# MICRO_AND_VREF.net
KiCad netlist of a schematic drawn in Altium Designer
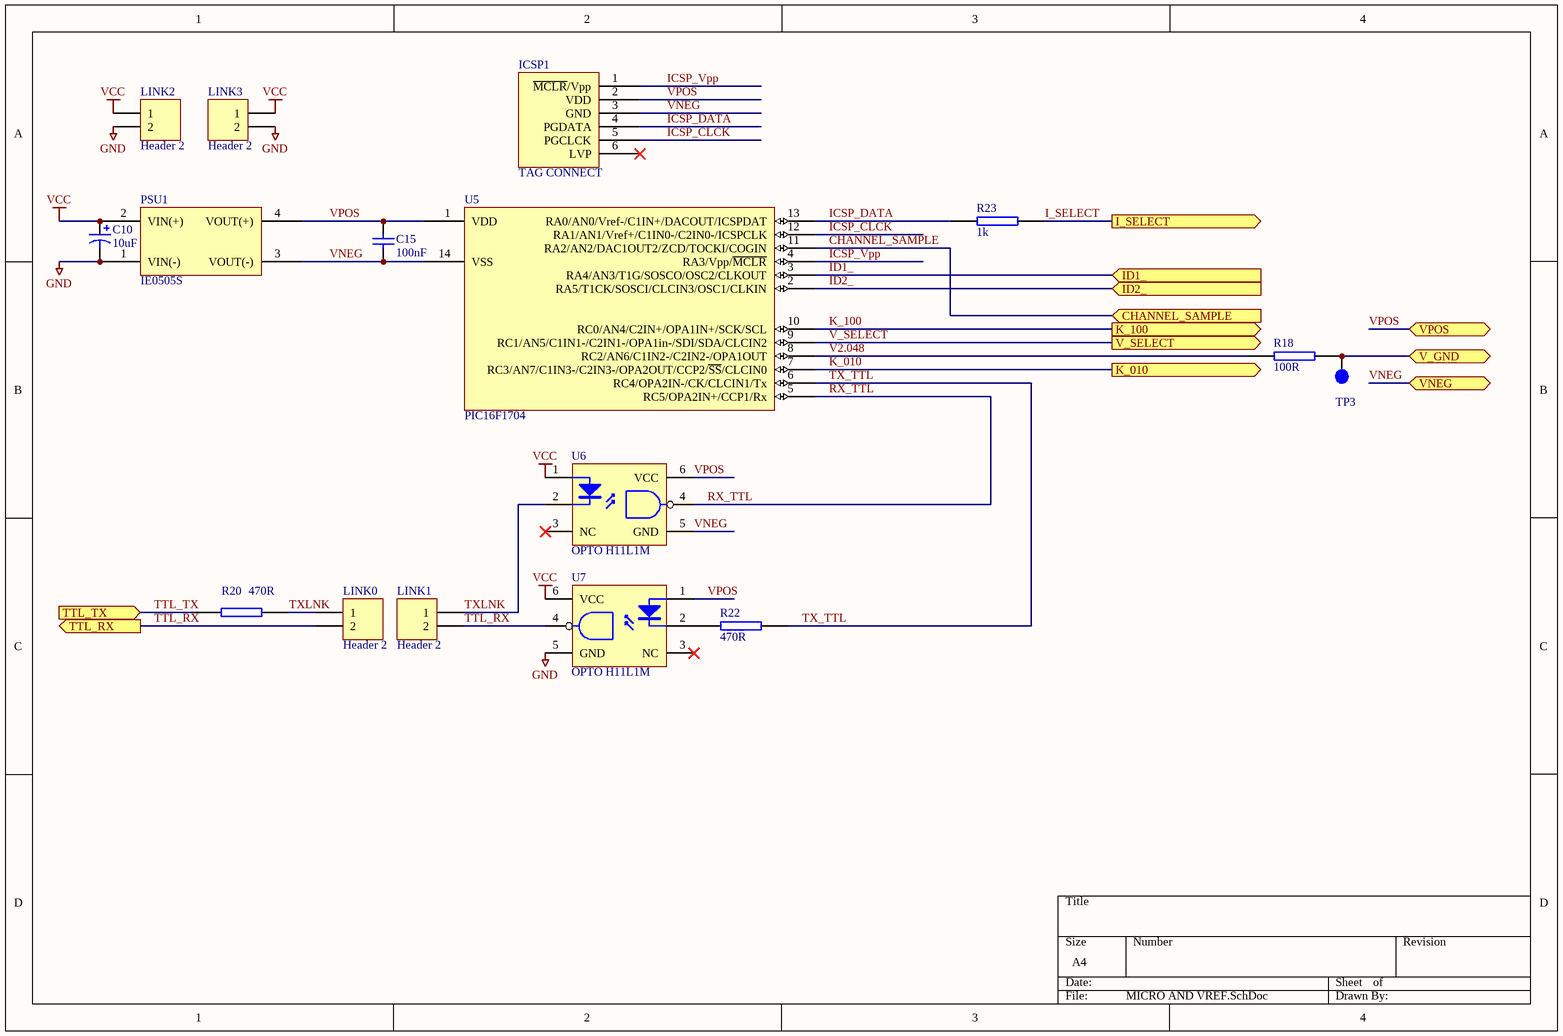
[diagram p0: MICRO AND VREF.SchDoc]

(export (version "E")
  (design (tool "Eeschema 10.0.6"))
  (components
    (comp (ref "C10")
      (value "10uF")
      (footprint "CAP ELECTRO SIZE-B")
      (description "Polarized Capacitor (Radial)")
      (libsource (lib "Miscellaneous Devices") (part "Cap Pol1"))
    )
    (comp (ref "C15")
      (value "100nF")
      (footprint "CAP (3D) - 0603")
      (description "Capacitor")
      (libsource (lib "Miscellaneous Devices") (part "Cap"))
    )
    (comp (ref "ICSP1")
      (value "TAG CONNECT")
      (footprint "ICSP - TAG CONNECT TYPE2")
      (fields (field (name "MANUFACTURER") "N/A - PCB ARTWORK"))
      (libsource (lib "I2C PENDANT") (part "ICSP - TAG CONNECT"))
    )
    (comp (ref "LINK0")
      (value "Header 2")
      (footprint "HDR1X2")
      (description "Header, 2-Pin")
      (fields (field (name "PUBLISHER") "Altium Limited"))
      (libsource (lib "Miscellaneous Connectors") (part "Header 2"))
    )
    (comp (ref "LINK1")
      (value "Header 2")
      (footprint "HDR1X2")
      (description "Header, 2-Pin")
      (fields (field (name "PUBLISHER") "Altium Limited"))
      (libsource (lib "") (part "Header 2_1"))
    )
    (comp (ref "LINK2")
      (value "Header 2")
      (footprint "HDR1X2")
      (description "Header, 2-Pin")
      (fields (field (name "PUBLISHER") "Altium Limited"))
      (libsource (lib "Miscellaneous Connectors") (part "Header 2"))
    )
    (comp (ref "LINK3")
      (value "Header 2")
      (footprint "HDR1X2")
      (description "Header, 2-Pin")
      (fields (field (name "PUBLISHER") "Altium Limited"))
      (libsource (lib "") (part "Header 2_1"))
    )
    (comp (ref "PSU1")
      (value "IE0505S")
      (footprint "IE0505S")
      (description "XP POWER IE0505S")
      (fields (field (name "FARNELL PART NO.") "8727694") (field (name "MANUFACTURER") "XP POWER"))
      (libsource (lib "Schlib1") (part "5V ISOLATED"))
    )
    (comp (ref "R18")
      (value "100R")
      (footprint "RES (3D) - 0603")
      (description "RESISTOR SMD 0603")
      (libsource (lib "NASCO") (part "RES SMD 0603"))
    )
    (comp (ref "R20")
      (value "470R")
      (footprint "RES (3D) - 0603")
      (description "RESISTOR SMD 0603 1k")
      (libsource (lib "NASCO Resistors") (part "RES SMD 0603 1k"))
    )
    (comp (ref "R22")
      (value "470R")
      (footprint "RES (3D) - 0603")
      (description "RESISTOR SMD 0603 1k")
      (libsource (lib "NASCO Resistors") (part "RES SMD 0603 1k"))
    )
    (comp (ref "R23")
      (value "1k")
      (footprint "RES (3D) - 0603")
      (description "RESISTOR SMD 0603")
      (libsource (lib "NASCO") (part "RES SMD 0603"))
    )
    (comp (ref "TP3") (value "TestPoint") (footprint "TP") (libsource (lib "NASCO") (part "TestPoint")))
    (comp (ref "U5")
      (value "PIC16F1704")
      (footprint "SOIC-14")
      (libsource (lib "Schlib1") (part "PIC16F1704"))
    )
    (comp (ref "U6")
      (value "OPTO H11L1M")
      (footprint "DIP_6")
      (description "6-Pin Logic Output Optocoupler")
      (libsource (lib "Schlib1") (part "H11L1M"))
    )
    (comp (ref "U7")
      (value "OPTO H11L1M")
      (footprint "DIP_6")
      (description "6-Pin Logic Output Optocoupler")
      (libsource (lib "") (part "H11L1M_1"))
    )
  )
  (nets
    (net (code "1") (name "/CHANNEL_SAMPLE") (class "Default")
      (node (ref "U5") (pin "11") (pinfunction "RA2/AN2/DAC1OUT2/ZCD/TOCKI/COGIN_11") (pintype "bidirectional"))
    )
    (net (code "2") (name "/ICSP_CLCK") (class "Default")
      (node (ref "ICSP1") (pin "5") (pinfunction "PGCLCK_5") (pintype "passive"))
      (node (ref "U5") (pin "12") (pinfunction "RA1/AN1/Vref+/C1IN0-/C2IN0-/ICSPCLK_12") (pintype "bidirectional"))
    )
    (net (code "3") (name "/ICSP_DATA") (class "Default")
      (node (ref "ICSP1") (pin "4") (pinfunction "PGDATA_4") (pintype "passive"))
      (node (ref "R23") (pin "1") (pinfunction "1_1") (pintype "passive"))
      (node (ref "U5") (pin "13") (pinfunction "RA0/AN0/Vref-/C1IN+/DACOUT/ICSPDAT_13") (pintype "bidirectional"))
    )
    (net (code "4") (name "/ICSP_Vpp") (class "Default")
      (node (ref "ICSP1") (pin "1") (pinfunction "~{MCLR}/Vpp_1") (pintype "passive"))
      (node (ref "U5") (pin "4") (pinfunction "RA3/Vpp/~{MCLR}_4") (pintype "bidirectional"))
    )
    (net (code "5") (name "/ID1_") (class "Default")
      (node (ref "U5") (pin "3") (pinfunction "RA4/AN3/T1G/SOSCO/OSC2/CLKOUT_3") (pintype "bidirectional"))
    )
    (net (code "6") (name "/ID2_") (class "Default")
      (node (ref "U5") (pin "2") (pinfunction "RA5/T1CK/SOSCI/CLCIN3/OSC1/CLKIN_2") (pintype "bidirectional"))
    )
    (net (code "7") (name "/I_SELECT") (class "Default")
      (node (ref "R23") (pin "2") (pinfunction "2_2") (pintype "passive"))
    )
    (net (code "8") (name "/K_010") (class "Default")
      (node (ref "U5") (pin "7") (pinfunction "RC3/AN7/C1IN3-/C2IN3-/OPA2OUT/CCP2/~{SS}/CLCIN0_7") (pintype "bidirectional"))
    )
    (net (code "9") (name "/K_100") (class "Default")
      (node (ref "U5") (pin "10") (pinfunction "RC0/AN4/C2IN+/OPA1IN+/SCK/SCL_10") (pintype "bidirectional"))
    )
    (net (code "10") (name "/RX_TTL") (class "Default")
      (node (ref "U5") (pin "5") (pinfunction "RC5/OPA2IN+/CCP1/Rx_5") (pintype "bidirectional"))
      (node (ref "U6") (pin "4") (pinfunction "Q_4") (pintype "passive"))
    )
    (net (code "11") (name "/TTL_RX") (class "Default")
      (node (ref "LINK0") (pin "2") (pinfunction "2_2") (pintype "passive"))
      (node (ref "LINK1") (pin "2") (pinfunction "2_2") (pintype "passive"))
      (node (ref "U7") (pin "4") (pinfunction "Q_4") (pintype "passive"))
    )
    (net (code "12") (name "/TTL_TX") (class "Default")
      (node (ref "R20") (pin "1") (pinfunction "1_1") (pintype "passive"))
    )
    (net (code "13") (name "/TXLNK") (class "Default")
      (node (ref "LINK0") (pin "1") (pinfunction "1_1") (pintype "passive"))
      (node (ref "LINK1") (pin "1") (pinfunction "1_1") (pintype "passive"))
      (node (ref "R20") (pin "2") (pinfunction "2_2") (pintype "passive"))
      (node (ref "U6") (pin "2") (pinfunction "K_2") (pintype "passive"))
    )
    (net (code "14") (name "/TX_TTL") (class "Default")
      (node (ref "R22") (pin "2") (pinfunction "2_2") (pintype "passive"))
      (node (ref "U5") (pin "6") (pinfunction "RC4/OPA2IN-/CK/CLCIN1/Tx_6") (pintype "bidirectional"))
    )
    (net (code "15") (name "/V2.048") (class "Default")
      (node (ref "R18") (pin "1") (pinfunction "1_1") (pintype "passive"))
      (node (ref "U5") (pin "8") (pinfunction "RC2/AN6/C1IN2-/C2IN2-/OPA1OUT_8") (pintype "bidirectional"))
    )
    (net (code "16") (name "/VNEG") (class "Default")
      (node (ref "C15") (pin "1") (pinfunction "1_1") (pintype "passive"))
      (node (ref "ICSP1") (pin "3") (pinfunction "GND_3") (pintype "passive"))
      (node (ref "PSU1") (pin "3") (pinfunction "VOUT(-)_3") (pintype "passive"))
      (node (ref "U5") (pin "14") (pinfunction "VSS_14") (pintype "power_in"))
      (node (ref "U6") (pin "5") (pinfunction "GND_5") (pintype "passive"))
    )
    (net (code "17") (name "/VPOS") (class "Default")
      (node (ref "C15") (pin "2") (pinfunction "2_2") (pintype "passive"))
      (node (ref "ICSP1") (pin "2") (pinfunction "VDD_2") (pintype "passive"))
      (node (ref "PSU1") (pin "4") (pinfunction "VOUT(+)_4") (pintype "passive"))
      (node (ref "U5") (pin "1") (pinfunction "VDD_1") (pintype "power_in"))
      (node (ref "U6") (pin "6") (pinfunction "VCC_6") (pintype "passive"))
      (node (ref "U7") (pin "1") (pinfunction "A_1") (pintype "passive"))
    )
    (net (code "18") (name "/V_GND") (class "Default")
      (node (ref "R18") (pin "2") (pinfunction "2_2") (pintype "passive"))
      (node (ref "TP3") (pin "1") (pinfunction "1_1") (pintype "passive"))
    )
    (net (code "19") (name "/V_SELECT") (class "Default")
      (node (ref "U5") (pin "9") (pinfunction "RC1/AN5/C1IN1-/C2IN1-/OPA1in-/SDI/SDA/CLCIN2_9") (pintype "bidirectional"))
    )
    (net (code "20") (name "GND") (class "Default")
      (node (ref "C10") (pin "2") (pinfunction "2_2") (pintype "passive"))
      (node (ref "LINK2") (pin "2") (pinfunction "2_2") (pintype "passive"))
      (node (ref "LINK3") (pin "2") (pinfunction "2_2") (pintype "passive"))
      (node (ref "PSU1") (pin "1") (pinfunction "VIN(-)_1") (pintype "passive"))
      (node (ref "U7") (pin "5") (pinfunction "GND_5") (pintype "passive"))
    )
    (net (code "21") (name "Net-(U7-K)") (class "Default")
      (node (ref "R22") (pin "1") (pinfunction "1_1") (pintype "passive"))
      (node (ref "U7") (pin "2") (pinfunction "K_2") (pintype "passive"))
    )
    (net (code "22") (name "VCC") (class "Default")
      (node (ref "C10") (pin "1") (pinfunction "1_1") (pintype "passive"))
      (node (ref "LINK2") (pin "1") (pinfunction "1_1") (pintype "passive"))
      (node (ref "LINK3") (pin "1") (pinfunction "1_1") (pintype "passive"))
      (node (ref "PSU1") (pin "2") (pinfunction "VIN(+)_2") (pintype "passive"))
      (node (ref "U6") (pin "1") (pinfunction "A_1") (pintype "passive"))
      (node (ref "U7") (pin "6") (pinfunction "VCC_6") (pintype "passive"))
    )
    (net (code "23") (name "unconnected-(ICSP1-LVP-Pad6)") (class "Default")
      (node (ref "ICSP1") (pin "6") (pinfunction "LVP_6") (pintype "passive+no_connect"))
    )
    (net (code "24") (name "unconnected-(U6-NC-Pad3)") (class "Default")
      (node (ref "U6") (pin "3") (pinfunction "NC_3") (pintype "passive+no_connect"))
    )
    (net (code "25") (name "unconnected-(U7-NC-Pad3)") (class "Default")
      (node (ref "U7") (pin "3") (pinfunction "NC_3") (pintype "passive+no_connect"))
    )
  )
)
